# ADCs.net
KiCad netlist of a schematic drawn in Altium Designer
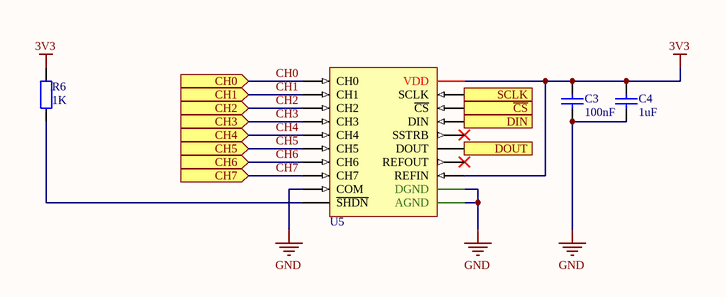
[diagram p0: ADCs.SchDoc]

(export (version "E")
  (design (tool "Eeschema 10.0.6"))
  (components
    (comp (ref "C3")
      (value "100nF")
      (footprint "FP_0805_CAP_085")
      (description "Capacitor")
      (fields (field (name "TOLERANCE") "+80%/-20%") (field (name "VOLTAGE") "25V"))
      (libsource (lib "hallglib") (part "CAP 100nF"))
    )
    (comp (ref "C4")
      (value "1uF")
      (footprint "FP_0805_CAP_085")
      (description "Capacitor")
      (fields (field (name "TOLERANCE") "+80%/-20%") (field (name "VOLTAGE") "25V"))
      (libsource (lib "hallglib") (part "CAP 1uF"))
    )
    (comp (ref "R6")
      (value "1K")
      (footprint "FP_0805_RES")
      (description "Resistor")
      (fields (field (name "TOLERANCE") "5%") (field (name "POWER") "125mW"))
      (libsource (lib "hallglib") (part "RES 1K"))
    )
    (comp (ref "U5")
      (value "MAX1110CAP+")
      (footprint "20-Pin SSOP")
      (description "Analogue to Digital Converter, Low Power, 8 bit, 50 kSPS, Single, 2.7 V, 5.5 V, SSOP")
      (libsource (lib "RobonAUT") (part "MAX1110CAP+"))
    )
  )
  (nets
    (net (code "1") (name "/CH0") (class "Default")
      (node (ref "U5") (pin "1") (pinfunction "CH0_1") (pintype "input"))
    )
    (net (code "2") (name "/CH1") (class "Default")
      (node (ref "U5") (pin "2") (pinfunction "CH1_2") (pintype "input"))
    )
    (net (code "3") (name "/CH2") (class "Default")
      (node (ref "U5") (pin "3") (pinfunction "CH2_3") (pintype "input"))
    )
    (net (code "4") (name "/CH3") (class "Default")
      (node (ref "U5") (pin "4") (pinfunction "CH3_4") (pintype "input"))
    )
    (net (code "5") (name "/CH4") (class "Default")
      (node (ref "U5") (pin "5") (pinfunction "CH4_5") (pintype "input"))
    )
    (net (code "6") (name "/CH5") (class "Default")
      (node (ref "U5") (pin "6") (pinfunction "CH5_6") (pintype "input"))
    )
    (net (code "7") (name "/CH6") (class "Default")
      (node (ref "U5") (pin "7") (pinfunction "CH6_7") (pintype "input"))
    )
    (net (code "8") (name "/CH7") (class "Default")
      (node (ref "U5") (pin "8") (pinfunction "CH7_8") (pintype "input"))
    )
    (net (code "9") (name "/DIN") (class "Default")
      (node (ref "U5") (pin "17") (pinfunction "DIN_17") (pintype "input"))
    )
    (net (code "10") (name "/DOUT") (class "Default")
      (node (ref "U5") (pin "15") (pinfunction "DOUT_15") (pintype "passive"))
    )
    (net (code "11") (name "/SCLK") (class "Default")
      (node (ref "U5") (pin "19") (pinfunction "SCLK_19") (pintype "input"))
    )
    (net (code "12") (name "/~{CS}") (class "Default")
      (node (ref "U5") (pin "18") (pinfunction "~{CS}_18") (pintype "input"))
    )
    (net (code "13") (name "3V3") (class "Default")
      (node (ref "C3") (pin "2") (pinfunction "2_2") (pintype "passive"))
      (node (ref "C4") (pin "2") (pinfunction "2_2") (pintype "passive"))
      (node (ref "R6") (pin "2") (pinfunction "2_2") (pintype "passive"))
      (node (ref "U5") (pin "11") (pinfunction "REFIN_11") (pintype "input"))
      (node (ref "U5") (pin "20") (pinfunction "VDD_20") (pintype "power_in"))
    )
    (net (code "14") (name "GND") (class "Default")
      (node (ref "C3") (pin "1") (pinfunction "1_1") (pintype "passive"))
      (node (ref "C4") (pin "1") (pinfunction "1_1") (pintype "passive"))
      (node (ref "U5") (pin "13") (pinfunction "AGND_13") (pintype "power_in"))
      (node (ref "U5") (pin "14") (pinfunction "DGND_14") (pintype "power_in"))
      (node (ref "U5") (pin "9") (pinfunction "COM_9") (pintype "input"))
    )
    (net (code "15") (name "Net-(U5-~{SHDN})") (class "Default")
      (node (ref "R6") (pin "1") (pinfunction "1_1") (pintype "passive"))
      (node (ref "U5") (pin "10") (pinfunction "~{SHDN}_10") (pintype "tri_state"))
    )
    (net (code "16") (name "unconnected-(U5-REFOUT-Pad12)") (class "Default")
      (node (ref "U5") (pin "12") (pinfunction "REFOUT_12") (pintype "output+no_connect"))
    )
    (net (code "17") (name "unconnected-(U5-SSTRB-Pad16)") (class "Default")
      (node (ref "U5") (pin "16") (pinfunction "SSTRB_16") (pintype "output+no_connect"))
    )
  )
)
